# schematic.net
KiCad netlist of a schematic drawn in EAGLE
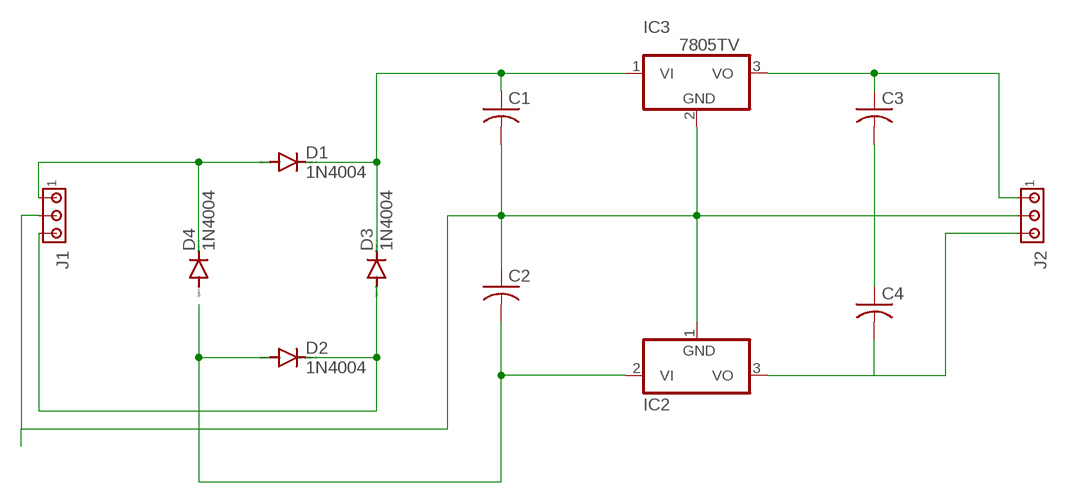
[diagram p0: schematic, sheet 1]

(export (version "E")
  (design (tool "Eeschema 10.0.6"))
  (components
    (comp (ref "C1")
      (value "C-US102-064X133")
      (footprint "eagle-import:C102-064X133")
      (libsource (lib "eagle-import") (part "C-US102-064X133"))
    )
    (comp (ref "C2")
      (value "C-US102-064X133")
      (footprint "eagle-import:C102-064X133")
      (libsource (lib "eagle-import") (part "C-US102-064X133"))
    )
    (comp (ref "C3")
      (value "C-US102-064X133")
      (footprint "eagle-import:C102-064X133")
      (libsource (lib "eagle-import") (part "C-US102-064X133"))
    )
    (comp (ref "C4")
      (value "C-US102-064X133")
      (footprint "eagle-import:C102-064X133")
      (libsource (lib "eagle-import") (part "C-US102-064X133"))
    )
    (comp (ref "D1")
      (value "1N4004")
      (footprint "eagle-import:DO41-10")
      (libsource (lib "eagle-import") (part "1N4004"))
    )
    (comp (ref "D2")
      (value "1N4004")
      (footprint "eagle-import:DO41-10")
      (libsource (lib "eagle-import") (part "1N4004"))
    )
    (comp (ref "D3")
      (value "1N4004")
      (footprint "eagle-import:DO41-10")
      (libsource (lib "eagle-import") (part "1N4004"))
    )
    (comp (ref "D4")
      (value "1N4004")
      (footprint "eagle-import:DO41-10")
      (libsource (lib "eagle-import") (part "1N4004"))
    )
    (comp (ref "IC2")
      (value "7908T")
      (footprint "eagle-import:TO220H")
      (libsource (lib "eagle-import") (part "79T08"))
    )
    (comp (ref "IC3")
      (value "7805TV")
      (footprint "eagle-import:TO220V")
      (libsource (lib "eagle-import") (part "78TV05"))
    )
    (comp (ref "J1")
      (value "MTA03-100")
      (footprint "eagle-import:10X03MTA")
      (libsource (lib "eagle-import") (part "MTA03-100"))
    )
    (comp (ref "J2")
      (value "MTA03-100")
      (footprint "eagle-import:10X03MTA")
      (libsource (lib "eagle-import") (part "MTA03-100"))
    )
  )
  (nets
    (net (code "1") (name "Net-(C3-Pad2)") (class "Default")
      (node (ref "C3") (pin "2") (pinfunction "2_2") (pintype "passive"))
      (node (ref "C4") (pin "1") (pinfunction "1_1") (pintype "passive"))
    )
    (net (code "2") (name "Net-(D1-PadA)") (class "Default")
      (node (ref "D1") (pin "A") (pinfunction "A_A") (pintype "passive"))
      (node (ref "D4") (pin "C") (pinfunction "C_C") (pintype "passive"))
      (node (ref "J1") (pin "1") (pinfunction "1_1") (pintype "passive"))
    )
    (net (code "3") (name "Net-(D2-PadC)") (class "Default")
      (node (ref "D2") (pin "C") (pinfunction "C_C") (pintype "passive"))
      (node (ref "D3") (pin "A") (pinfunction "A_A") (pintype "passive"))
      (node (ref "J1") (pin "3") (pinfunction "3_3") (pintype "passive"))
    )
    (net (code "4") (name "Net-(IC2-GND)") (class "Default")
      (node (ref "C1") (pin "2") (pinfunction "2_2") (pintype "passive"))
      (node (ref "C2") (pin "1") (pinfunction "1_1") (pintype "passive"))
      (node (ref "IC2") (pin "1") (pinfunction "GND_1") (pintype "passive"))
      (node (ref "IC3") (pin "2") (pinfunction "GND_2") (pintype "passive"))
      (node (ref "J1") (pin "2") (pinfunction "2_2") (pintype "passive"))
      (node (ref "J2") (pin "2") (pinfunction "2_2") (pintype "passive"))
    )
    (net (code "5") (name "Net-(IC2-VI)") (class "Default")
      (node (ref "C2") (pin "2") (pinfunction "2_2") (pintype "passive"))
      (node (ref "D2") (pin "A") (pinfunction "A_A") (pintype "passive"))
      (node (ref "IC2") (pin "2") (pinfunction "VI_2") (pintype "input"))
    )
    (net (code "6") (name "Net-(IC2-VO)") (class "Default")
      (node (ref "IC2") (pin "3") (pinfunction "VO_3") (pintype "passive"))
      (node (ref "J2") (pin "3") (pinfunction "3_3") (pintype "passive"))
    )
    (net (code "7") (name "Net-(IC3-VI)") (class "Default")
      (node (ref "C1") (pin "1") (pinfunction "1_1") (pintype "passive"))
      (node (ref "D1") (pin "C") (pinfunction "C_C") (pintype "passive"))
      (node (ref "D3") (pin "C") (pinfunction "C_C") (pintype "passive"))
      (node (ref "IC3") (pin "1") (pinfunction "VI_1") (pintype "input"))
    )
    (net (code "8") (name "Net-(IC3-VO)") (class "Default")
      (node (ref "C3") (pin "1") (pinfunction "1_1") (pintype "passive"))
      (node (ref "IC3") (pin "3") (pinfunction "VO_3") (pintype "passive"))
      (node (ref "J2") (pin "1") (pinfunction "1_1") (pintype "passive"))
    )
    (net (code "9") (name "unconnected-(C4-Pad2)") (class "Default")
      (node (ref "C4") (pin "2") (pinfunction "2_2") (pintype "passive"))
    )
    (net (code "10") (name "unconnected-(D4-PadA)") (class "Default")
      (node (ref "D4") (pin "A") (pinfunction "A_A") (pintype "passive"))
    )
  )
)
